# Smarttree_CMU_6.net
KiCad netlist of a schematic drawn in EAGLE
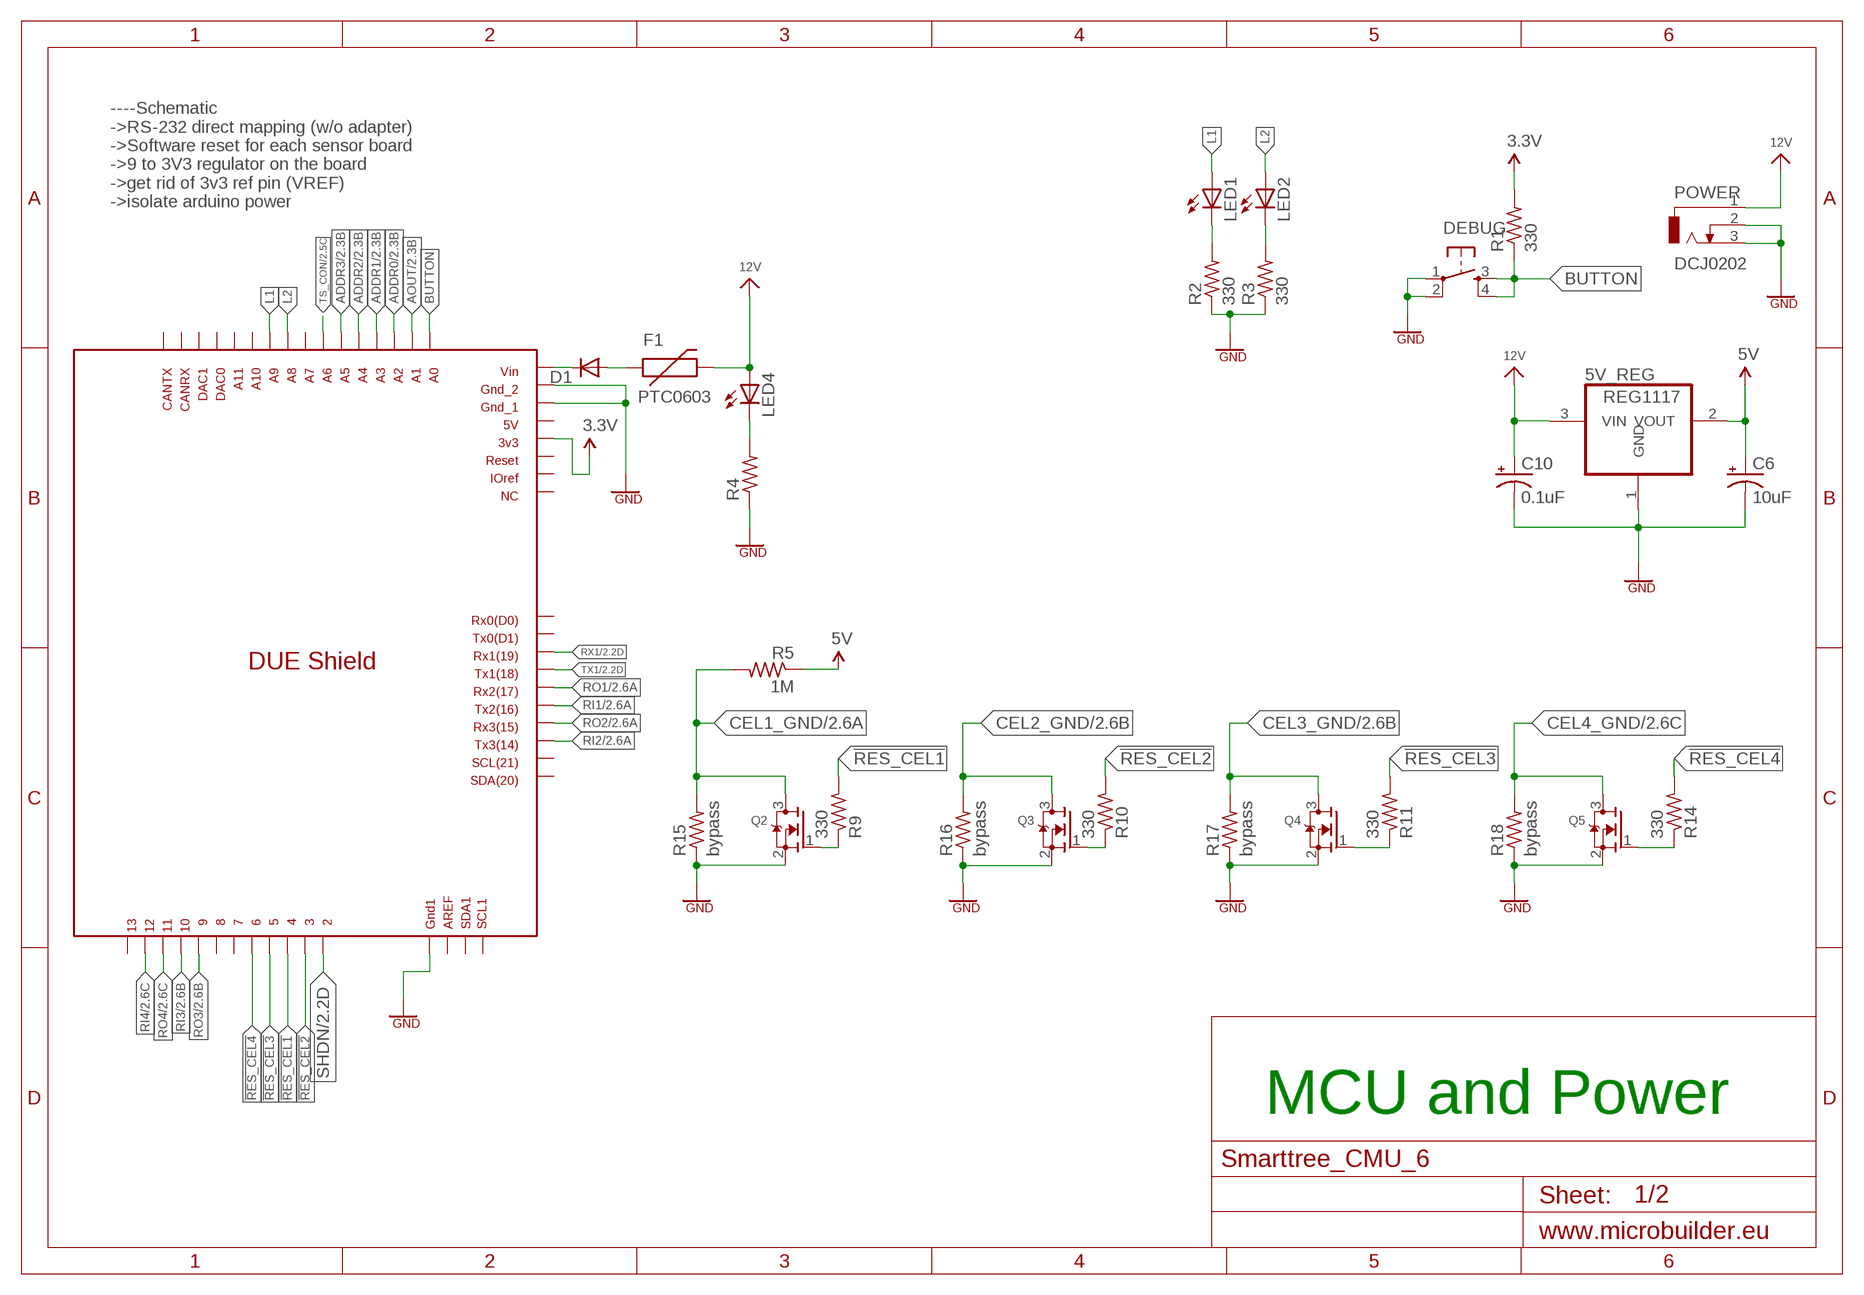
[diagram p0: schematic, sheet 1]
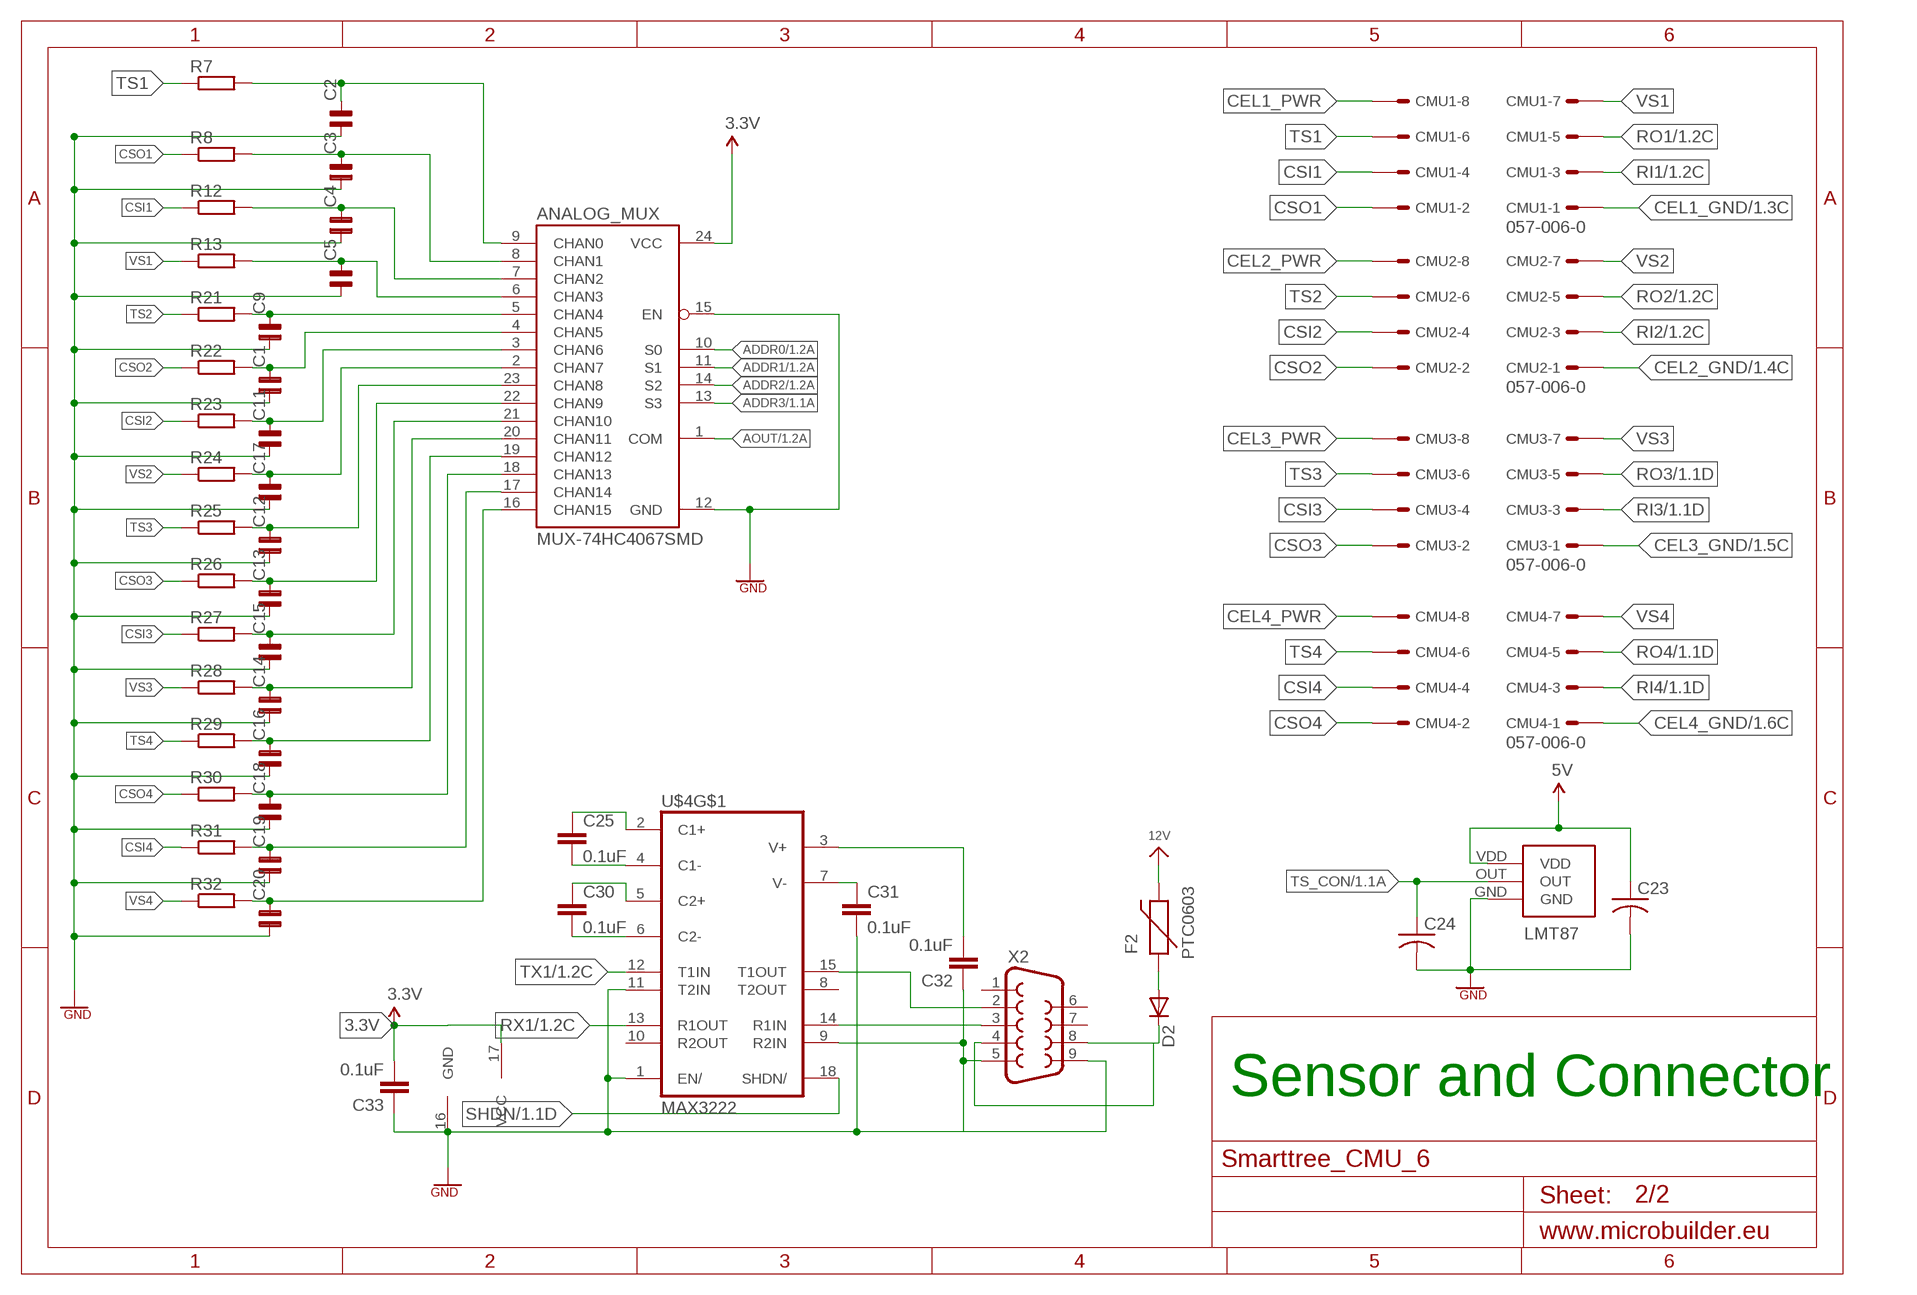
[diagram p1: schematic, sheet 2]

(export (version "E")
  (design (tool "Eeschema 10.0.6"))
  (components
    (comp (ref "5V_REG")
      (value "REG1117")
      (footprint "eagle-import:SOT223")
      (libsource (lib "eagle-import") (part "REG1117"))
    )
    (comp (ref "C6")
      (value "10uF")
      (footprint "eagle-import:EIA3216")
      (libsource (lib "eagle-import") (part "10UF-TANT"))
    )
    (comp (ref "C10")
      (value "0.1uF")
      (footprint "eagle-import:EIA3216")
      (libsource (lib "eagle-import") (part "10UF-TANT"))
    )
    (comp (ref "D1")
      (value "DIODE-SOD106-R")
      (footprint "eagle-import:SOD106-R")
      (libsource (lib "eagle-import") (part "DIODE-SOD106-R"))
    )
    (comp (ref "DEBUG")
      (value "TAC_SWITCHSMD")
      (footprint "eagle-import:TACTILE_SWITCH_SMD")
      (libsource (lib "eagle-import") (part "TAC_SWITCHSMD"))
    )
    (comp (ref "F1")
      (value "PTC0603")
      (footprint "eagle-import:0603")
      (libsource (lib "eagle-import") (part "PTC0603"))
    )
    (comp (ref "LED1")
      (value "LED-YELLOW0603")
      (footprint "eagle-import:LED-0603")
      (libsource (lib "eagle-import") (part "LED-YELLOW0603"))
    )
    (comp (ref "LED2")
      (value "LED-YELLOW0603")
      (footprint "eagle-import:LED-0603")
      (libsource (lib "eagle-import") (part "LED-YELLOW0603"))
    )
    (comp (ref "LED4")
      (value "LED-YELLOW0603")
      (footprint "eagle-import:LED-0603")
      (libsource (lib "eagle-import") (part "LED-YELLOW0603"))
    )
    (comp (ref "POWER")
      (value "DCJ0202")
      (footprint "eagle-import:DCJ0202")
      (libsource (lib "eagle-import") (part "DCJ0202"))
    )
    (comp (ref "Q2")
      (value "MOSFET-NREFLOW")
      (footprint "eagle-import:SOT23")
      (libsource (lib "eagle-import") (part "MOSFET-NREFLOW"))
    )
    (comp (ref "Q3")
      (value "MOSFET-NREFLOW")
      (footprint "eagle-import:SOT23")
      (libsource (lib "eagle-import") (part "MOSFET-NREFLOW"))
    )
    (comp (ref "Q4")
      (value "MOSFET-NREFLOW")
      (footprint "eagle-import:SOT23")
      (libsource (lib "eagle-import") (part "MOSFET-NREFLOW"))
    )
    (comp (ref "Q5")
      (value "MOSFET-NREFLOW")
      (footprint "eagle-import:SOT23")
      (libsource (lib "eagle-import") (part "MOSFET-NREFLOW"))
    )
    (comp (ref "R1")
      (value "330")
      (footprint "eagle-import:M0805")
      (libsource (lib "eagle-import") (part "R-US_M0805"))
    )
    (comp (ref "R2")
      (value "330")
      (footprint "eagle-import:M0805")
      (libsource (lib "eagle-import") (part "R-US_M0805"))
    )
    (comp (ref "R3")
      (value "330")
      (footprint "eagle-import:M0805")
      (libsource (lib "eagle-import") (part "R-US_M0805"))
    )
    (comp (ref "R4")
      (value "R-US_M0805")
      (footprint "eagle-import:M0805")
      (libsource (lib "eagle-import") (part "R-US_M0805"))
    )
    (comp (ref "R5")
      (value "1M")
      (footprint "eagle-import:R0805")
      (libsource (lib "eagle-import") (part "R-US_R0805"))
    )
    (comp (ref "R9")
      (value "330")
      (footprint "eagle-import:R0805")
      (libsource (lib "eagle-import") (part "R-US_R0805"))
    )
    (comp (ref "R10")
      (value "330")
      (footprint "eagle-import:R0805")
      (libsource (lib "eagle-import") (part "R-US_R0805"))
    )
    (comp (ref "R11")
      (value "330")
      (footprint "eagle-import:R0805")
      (libsource (lib "eagle-import") (part "R-US_R0805"))
    )
    (comp (ref "R14")
      (value "330")
      (footprint "eagle-import:R0805")
      (libsource (lib "eagle-import") (part "R-US_R0805"))
    )
    (comp (ref "R15")
      (value "bypass")
      (footprint "eagle-import:M0805")
      (libsource (lib "eagle-import") (part "R-US_M0805"))
    )
    (comp (ref "R16")
      (value "bypass")
      (footprint "eagle-import:M0805")
      (libsource (lib "eagle-import") (part "R-US_M0805"))
    )
    (comp (ref "R17")
      (value "bypass")
      (footprint "eagle-import:M0805")
      (libsource (lib "eagle-import") (part "R-US_M0805"))
    )
    (comp (ref "R18")
      (value "bypass")
      (footprint "eagle-import:M0805")
      (libsource (lib "eagle-import") (part "R-US_M0805"))
    )
    (comp (ref "U$1")
      (value "DUE(OUTLINE)")
      (footprint "eagle-import:DUE(NORMAL)")
      (libsource (lib "eagle-import") (part "DUE(OUTLINE)"))
    )
    (comp (ref "ANALOG_MUX")
      (value "MUX-74HC4067SMD")
      (footprint "eagle-import:SSOP24")
      (libsource (lib "eagle-import") (part "MUX-74HC4067SMD"))
    )
    (comp (ref "C1")
      (value "C-NP-SMD-0805")
      (footprint "eagle-import:C-0805")
      (libsource (lib "eagle-import") (part "C-NP-SMD-0805"))
    )
    (comp (ref "C2")
      (value "C-NP-SMD-0805")
      (footprint "eagle-import:C-0805")
      (libsource (lib "eagle-import") (part "C-NP-SMD-0805"))
    )
    (comp (ref "C3")
      (value "C-NP-SMD-0805")
      (footprint "eagle-import:C-0805")
      (libsource (lib "eagle-import") (part "C-NP-SMD-0805"))
    )
    (comp (ref "C4")
      (value "C-NP-SMD-0805")
      (footprint "eagle-import:C-0805")
      (libsource (lib "eagle-import") (part "C-NP-SMD-0805"))
    )
    (comp (ref "C5")
      (value "C-NP-SMD-0805")
      (footprint "eagle-import:C-0805")
      (libsource (lib "eagle-import") (part "C-NP-SMD-0805"))
    )
    (comp (ref "C9")
      (value "C-NP-SMD-0805")
      (footprint "eagle-import:C-0805")
      (libsource (lib "eagle-import") (part "C-NP-SMD-0805"))
    )
    (comp (ref "C11")
      (value "C-NP-SMD-0805")
      (footprint "eagle-import:C-0805")
      (libsource (lib "eagle-import") (part "C-NP-SMD-0805"))
    )
    (comp (ref "C12")
      (value "C-NP-SMD-0805")
      (footprint "eagle-import:C-0805")
      (libsource (lib "eagle-import") (part "C-NP-SMD-0805"))
    )
    (comp (ref "C13")
      (value "C-NP-SMD-0805")
      (footprint "eagle-import:C-0805")
      (libsource (lib "eagle-import") (part "C-NP-SMD-0805"))
    )
    (comp (ref "C14")
      (value "C-NP-SMD-0805")
      (footprint "eagle-import:C-0805")
      (libsource (lib "eagle-import") (part "C-NP-SMD-0805"))
    )
    (comp (ref "C15")
      (value "C-NP-SMD-0805")
      (footprint "eagle-import:C-0805")
      (libsource (lib "eagle-import") (part "C-NP-SMD-0805"))
    )
    (comp (ref "C16")
      (value "C-NP-SMD-0805")
      (footprint "eagle-import:C-0805")
      (libsource (lib "eagle-import") (part "C-NP-SMD-0805"))
    )
    (comp (ref "C17")
      (value "C-NP-SMD-0805")
      (footprint "eagle-import:C-0805")
      (libsource (lib "eagle-import") (part "C-NP-SMD-0805"))
    )
    (comp (ref "C18")
      (value "C-NP-SMD-0805")
      (footprint "eagle-import:C-0805")
      (libsource (lib "eagle-import") (part "C-NP-SMD-0805"))
    )
    (comp (ref "C19")
      (value "C-NP-SMD-0805")
      (footprint "eagle-import:C-0805")
      (libsource (lib "eagle-import") (part "C-NP-SMD-0805"))
    )
    (comp (ref "C20")
      (value "C-NP-SMD-0805")
      (footprint "eagle-import:C-0805")
      (libsource (lib "eagle-import") (part "C-NP-SMD-0805"))
    )
    (comp (ref "C23")
      (value "C-USC0805")
      (footprint "eagle-import:C0805")
      (libsource (lib "eagle-import") (part "C-USC0805"))
    )
    (comp (ref "C24")
      (value "C-USC0805")
      (footprint "eagle-import:C0805")
      (libsource (lib "eagle-import") (part "C-USC0805"))
    )
    (comp (ref "C25")
      (value "0.1uF")
      (footprint "eagle-import:0603-CAP")
      (libsource (lib "eagle-import") (part "CAP0603-CAP"))
    )
    (comp (ref "C30")
      (value "0.1uF")
      (footprint "eagle-import:0603-CAP")
      (libsource (lib "eagle-import") (part "CAP0603-CAP"))
    )
    (comp (ref "C31")
      (value "0.1uF")
      (footprint "eagle-import:0603-CAP")
      (libsource (lib "eagle-import") (part "CAP0603-CAP"))
    )
    (comp (ref "C32")
      (value "0.1uF")
      (footprint "eagle-import:0603-CAP")
      (libsource (lib "eagle-import") (part "CAP0603-CAP"))
    )
    (comp (ref "C33")
      (value "0.1uF")
      (footprint "eagle-import:0603-CAP")
      (libsource (lib "eagle-import") (part "CAP0603-CAP"))
    )
    (comp (ref "CMU1")
      (value "057-006-0")
      (footprint "eagle-import:057-006-0")
      (libsource (lib "eagle-import") (part "057-006-0"))
    )
    (comp (ref "CMU2")
      (value "057-006-0")
      (footprint "eagle-import:057-006-0")
      (libsource (lib "eagle-import") (part "057-006-0"))
    )
    (comp (ref "CMU3")
      (value "057-006-0")
      (footprint "eagle-import:057-006-0")
      (libsource (lib "eagle-import") (part "057-006-0"))
    )
    (comp (ref "CMU4")
      (value "057-006-0")
      (footprint "eagle-import:057-006-0")
      (libsource (lib "eagle-import") (part "057-006-0"))
    )
    (comp (ref "D2")
      (value "DIODE-SOD106-R")
      (footprint "eagle-import:SOD106-R")
      (libsource (lib "eagle-import") (part "DIODE-SOD106-R"))
    )
    (comp (ref "F2")
      (value "PTC0603")
      (footprint "eagle-import:0603")
      (libsource (lib "eagle-import") (part "PTC0603"))
    )
    (comp (ref "LMT87")
      (value "LMT87_PAC")
      (footprint "eagle-import:LMT87_TO")
      (libsource (lib "eagle-import") (part "LMT87_PAC"))
    )
    (comp (ref "R7")
      (value "R-EU_R0805W")
      (footprint "eagle-import:R0805W")
      (libsource (lib "eagle-import") (part "R-EU_R0805W"))
    )
    (comp (ref "R8")
      (value "R-EU_R0805W")
      (footprint "eagle-import:R0805W")
      (libsource (lib "eagle-import") (part "R-EU_R0805W"))
    )
    (comp (ref "R12")
      (value "R-EU_R0805W")
      (footprint "eagle-import:R0805W")
      (libsource (lib "eagle-import") (part "R-EU_R0805W"))
    )
    (comp (ref "R13")
      (value "R-EU_R0805W")
      (footprint "eagle-import:R0805W")
      (libsource (lib "eagle-import") (part "R-EU_R0805W"))
    )
    (comp (ref "R21")
      (value "R-EU_R0805W")
      (footprint "eagle-import:R0805W")
      (libsource (lib "eagle-import") (part "R-EU_R0805W"))
    )
    (comp (ref "R22")
      (value "R-EU_R0805W")
      (footprint "eagle-import:R0805W")
      (libsource (lib "eagle-import") (part "R-EU_R0805W"))
    )
    (comp (ref "R23")
      (value "R-EU_R0805W")
      (footprint "eagle-import:R0805W")
      (libsource (lib "eagle-import") (part "R-EU_R0805W"))
    )
    (comp (ref "R24")
      (value "R-EU_R0805W")
      (footprint "eagle-import:R0805W")
      (libsource (lib "eagle-import") (part "R-EU_R0805W"))
    )
    (comp (ref "R25")
      (value "R-EU_R0805W")
      (footprint "eagle-import:R0805W")
      (libsource (lib "eagle-import") (part "R-EU_R0805W"))
    )
    (comp (ref "R26")
      (value "R-EU_R0805W")
      (footprint "eagle-import:R0805W")
      (libsource (lib "eagle-import") (part "R-EU_R0805W"))
    )
    (comp (ref "R27")
      (value "R-EU_R0805W")
      (footprint "eagle-import:R0805W")
      (libsource (lib "eagle-import") (part "R-EU_R0805W"))
    )
    (comp (ref "R28")
      (value "R-EU_R0805W")
      (footprint "eagle-import:R0805W")
      (libsource (lib "eagle-import") (part "R-EU_R0805W"))
    )
    (comp (ref "R29")
      (value "R-EU_R0805W")
      (footprint "eagle-import:R0805W")
      (libsource (lib "eagle-import") (part "R-EU_R0805W"))
    )
    (comp (ref "R30")
      (value "R-EU_R0805W")
      (footprint "eagle-import:R0805W")
      (libsource (lib "eagle-import") (part "R-EU_R0805W"))
    )
    (comp (ref "R31")
      (value "R-EU_R0805W")
      (footprint "eagle-import:R0805W")
      (libsource (lib "eagle-import") (part "R-EU_R0805W"))
    )
    (comp (ref "R32")
      (value "R-EU_R0805W")
      (footprint "eagle-import:R0805W")
      (libsource (lib "eagle-import") (part "R-EU_R0805W"))
    )
    (comp (ref "U$4")
      (value "MAX3222")
      (footprint "eagle-import:SO18")
      (libsource (lib "eagle-import") (part "MAX3222"))
    )
    (comp (ref "X2")
      (value "DB9MALE")
      (footprint "eagle-import:DB9_MALE")
      (libsource (lib "eagle-import") (part "DB9MALE"))
    )
  )
  (nets
    (net (code "1") (name "3.3V") (class "Default")
      (node (ref "ANALOG_MUX") (pin "24") (pinfunction "VCC_24") (pintype "bidirectional"))
      (node (ref "C33") (pin "2") (pinfunction "2_2") (pintype "passive"))
      (node (ref "R1") (pin "2") (pinfunction "2_2") (pintype "passive"))
      (node (ref "U$1") (pin "3V3") (pinfunction "3V3_3V3") (pintype "bidirectional"))
      (node (ref "U$4") (pin "17") (pinfunction "VCC_17") (pintype "bidirectional"))
    )
    (net (code "2") (name "5V") (class "Default")
      (node (ref "5V_REG") (pin "2") (pinfunction "VOUT_2") (pintype "output"))
      (node (ref "C23") (pin "1") (pinfunction "1_1") (pintype "passive"))
      (node (ref "C6") (pin "A") (pinfunction "+_A") (pintype "passive"))
      (node (ref "LMT87") (pin "VDD") (pinfunction "VDD_VDD") (pintype "bidirectional"))
      (node (ref "R5") (pin "1") (pinfunction "1_1") (pintype "passive"))
    )
    (net (code "3") (name "12V") (class "Default")
      (node (ref "5V_REG") (pin "3") (pinfunction "VIN_3") (pintype "input"))
      (node (ref "C10") (pin "A") (pinfunction "+_A") (pintype "passive"))
      (node (ref "F1") (pin "2") (pinfunction "2_2") (pintype "bidirectional"))
      (node (ref "F2") (pin "2") (pinfunction "2_2") (pintype "bidirectional"))
      (node (ref "LED4") (pin "A") (pinfunction "A_A") (pintype "passive"))
      (node (ref "POWER") (pin "1") (pinfunction "1_1") (pintype "passive"))
    )
    (net (code "4") (name "ADDR0") (class "Default")
      (node (ref "ANALOG_MUX") (pin "10") (pinfunction "S0_10") (pintype "input"))
      (node (ref "U$1") (pin "A2") (pinfunction "A2_A2") (pintype "bidirectional"))
    )
    (net (code "5") (name "ADDR1") (class "Default")
      (node (ref "ANALOG_MUX") (pin "11") (pinfunction "S1_11") (pintype "input"))
      (node (ref "U$1") (pin "A3") (pinfunction "A3_A3") (pintype "bidirectional"))
    )
    (net (code "6") (name "ADDR2") (class "Default")
      (node (ref "ANALOG_MUX") (pin "14") (pinfunction "S2_14") (pintype "input"))
      (node (ref "U$1") (pin "A4") (pinfunction "A4_A4") (pintype "bidirectional"))
    )
    (net (code "7") (name "ADDR3") (class "Default")
      (node (ref "ANALOG_MUX") (pin "13") (pinfunction "S3_13") (pintype "input"))
      (node (ref "U$1") (pin "A5") (pinfunction "A5_A5") (pintype "bidirectional"))
    )
    (net (code "8") (name "AOUT") (class "Default")
      (node (ref "ANALOG_MUX") (pin "1") (pinfunction "COM_1") (pintype "bidirectional"))
      (node (ref "U$1") (pin "A1") (pinfunction "A1_A1") (pintype "bidirectional"))
    )
    (net (code "9") (name "BUTTON") (class "Default")
      (node (ref "DEBUG") (pin "3") (pinfunction "3_3") (pintype "passive"))
      (node (ref "DEBUG") (pin "4") (pinfunction "4_4") (pintype "passive"))
      (node (ref "R1") (pin "1") (pinfunction "1_1") (pintype "passive"))
      (node (ref "U$1") (pin "A0") (pinfunction "A0_A0") (pintype "bidirectional"))
    )
    (net (code "10") (name "CEL1_GND") (class "Default")
      (node (ref "CMU1") (pin "1") (pinfunction "S_1") (pintype "passive"))
      (node (ref "Q2") (pin "3") (pinfunction "D_3") (pintype "bidirectional"))
      (node (ref "R15") (pin "2") (pinfunction "2_2") (pintype "passive"))
      (node (ref "R5") (pin "2") (pinfunction "2_2") (pintype "passive"))
    )
    (net (code "11") (name "CEL1_PWR") (class "Default")
      (node (ref "CMU1") (pin "7") (pinfunction "S_7") (pintype "passive"))
    )
    (net (code "12") (name "CEL2_GND") (class "Default")
      (node (ref "CMU2") (pin "1") (pinfunction "S_1") (pintype "passive"))
      (node (ref "Q3") (pin "3") (pinfunction "D_3") (pintype "bidirectional"))
      (node (ref "R16") (pin "2") (pinfunction "2_2") (pintype "passive"))
    )
    (net (code "13") (name "CEL2_PWR") (class "Default")
      (node (ref "CMU2") (pin "7") (pinfunction "S_7") (pintype "passive"))
    )
    (net (code "14") (name "CEL3_GND") (class "Default")
      (node (ref "CMU3") (pin "1") (pinfunction "S_1") (pintype "passive"))
      (node (ref "Q4") (pin "3") (pinfunction "D_3") (pintype "bidirectional"))
      (node (ref "R17") (pin "2") (pinfunction "2_2") (pintype "passive"))
    )
    (net (code "15") (name "CEL3_PWR") (class "Default")
      (node (ref "CMU3") (pin "7") (pinfunction "S_7") (pintype "passive"))
    )
    (net (code "16") (name "CEL4_GND") (class "Default")
      (node (ref "CMU4") (pin "1") (pinfunction "S_1") (pintype "passive"))
      (node (ref "Q5") (pin "3") (pinfunction "D_3") (pintype "bidirectional"))
      (node (ref "R18") (pin "2") (pinfunction "2_2") (pintype "passive"))
    )
    (net (code "17") (name "CEL4_PWR") (class "Default")
      (node (ref "CMU4") (pin "7") (pinfunction "S_7") (pintype "passive"))
    )
    (net (code "18") (name "CSI1") (class "Default")
      (node (ref "CMU1") (pin "4") (pinfunction "S_4") (pintype "passive"))
      (node (ref "R12") (pin "1") (pinfunction "1_1") (pintype "passive"))
    )
    (net (code "19") (name "CSI2") (class "Default")
      (node (ref "CMU2") (pin "4") (pinfunction "S_4") (pintype "passive"))
      (node (ref "R23") (pin "1") (pinfunction "1_1") (pintype "passive"))
    )
    (net (code "20") (name "CSI3") (class "Default")
      (node (ref "CMU3") (pin "4") (pinfunction "S_4") (pintype "passive"))
      (node (ref "R27") (pin "1") (pinfunction "1_1") (pintype "passive"))
    )
    (net (code "21") (name "CSI4") (class "Default")
      (node (ref "CMU4") (pin "4") (pinfunction "S_4") (pintype "passive"))
      (node (ref "R31") (pin "1") (pinfunction "1_1") (pintype "passive"))
    )
    (net (code "22") (name "CSO1") (class "Default")
      (node (ref "CMU1") (pin "2") (pinfunction "S_2") (pintype "passive"))
      (node (ref "R8") (pin "1") (pinfunction "1_1") (pintype "passive"))
    )
    (net (code "23") (name "CSO2") (class "Default")
      (node (ref "CMU2") (pin "2") (pinfunction "S_2") (pintype "passive"))
      (node (ref "R22") (pin "1") (pinfunction "1_1") (pintype "passive"))
    )
    (net (code "24") (name "CSO3") (class "Default")
      (node (ref "CMU3") (pin "2") (pinfunction "S_2") (pintype "passive"))
      (node (ref "R26") (pin "1") (pinfunction "1_1") (pintype "passive"))
    )
    (net (code "25") (name "CSO4") (class "Default")
      (node (ref "CMU4") (pin "2") (pinfunction "S_2") (pintype "passive"))
      (node (ref "R30") (pin "1") (pinfunction "1_1") (pintype "passive"))
    )
    (net (code "26") (name "GND") (class "Default")
      (node (ref "5V_REG") (pin "1") (pinfunction "GND_1") (pintype "power_in"))
      (node (ref "ANALOG_MUX") (pin "12") (pinfunction "GND_12") (pintype "bidirectional"))
      (node (ref "ANALOG_MUX") (pin "15") (pinfunction "EN_15") (pintype "input"))
      (node (ref "C1") (pin "1") (pinfunction "1_1") (pintype "passive"))
      (node (ref "C10") (pin "C") (pinfunction "-_C") (pintype "passive"))
      (node (ref "C11") (pin "1") (pinfunction "1_1") (pintype "passive"))
      (node (ref "C12") (pin "1") (pinfunction "1_1") (pintype "passive"))
      (node (ref "C13") (pin "1") (pinfunction "1_1") (pintype "passive"))
      (node (ref "C14") (pin "1") (pinfunction "1_1") (pintype "passive"))
      (node (ref "C15") (pin "1") (pinfunction "1_1") (pintype "passive"))
      (node (ref "C16") (pin "1") (pinfunction "1_1") (pintype "passive"))
      (node (ref "C17") (pin "1") (pinfunction "1_1") (pintype "passive"))
      (node (ref "C18") (pin "1") (pinfunction "1_1") (pintype "passive"))
      (node (ref "C19") (pin "1") (pinfunction "1_1") (pintype "passive"))
      (node (ref "C2") (pin "1") (pinfunction "1_1") (pintype "passive"))
      (node (ref "C20") (pin "1") (pinfunction "1_1") (pintype "passive"))
      (node (ref "C23") (pin "2") (pinfunction "2_2") (pintype "passive"))
      (node (ref "C24") (pin "2") (pinfunction "2_2") (pintype "passive"))
      (node (ref "C3") (pin "1") (pinfunction "1_1") (pintype "passive"))
      (node (ref "C31") (pin "2") (pinfunction "2_2") (pintype "passive"))
      (node (ref "C32") (pin "1") (pinfunction "1_1") (pintype "passive"))
      (node (ref "C33") (pin "1") (pinfunction "1_1") (pintype "passive"))
      (node (ref "C4") (pin "1") (pinfunction "1_1") (pintype "passive"))
      (node (ref "C5") (pin "1") (pinfunction "1_1") (pintype "passive"))
      (node (ref "C6") (pin "C") (pinfunction "-_C") (pintype "passive"))
      (node (ref "C9") (pin "1") (pinfunction "1_1") (pintype "passive"))
      (node (ref "DEBUG") (pin "1") (pinfunction "1_1") (pintype "passive"))
      (node (ref "DEBUG") (pin "2") (pinfunction "2_2") (pintype "passive"))
      (node (ref "LMT87") (pin "GND") (pinfunction "GND_GND") (pintype "bidirectional"))
      (node (ref "POWER") (pin "2") (pinfunction "2_2") (pintype "passive"))
      (node (ref "POWER") (pin "3") (pinfunction "3_3") (pintype "passive"))
      (node (ref "Q2") (pin "2") (pinfunction "S_2") (pintype "bidirectional"))
      (node (ref "Q3") (pin "2") (pinfunction "S_2") (pintype "bidirectional"))
      (node (ref "Q4") (pin "2") (pinfunction "S_2") (pintype "bidirectional"))
      (node (ref "Q5") (pin "2") (pinfunction "S_2") (pintype "bidirectional"))
      (node (ref "R15") (pin "1") (pinfunction "1_1") (pintype "passive"))
      (node (ref "R16") (pin "1") (pinfunction "1_1") (pintype "passive"))
      (node (ref "R17") (pin "1") (pinfunction "1_1") (pintype "passive"))
      (node (ref "R18") (pin "1") (pinfunction "1_1") (pintype "passive"))
      (node (ref "R2") (pin "1") (pinfunction "1_1") (pintype "passive"))
      (node (ref "R3") (pin "1") (pinfunction "1_1") (pintype "passive"))
      (node (ref "R4") (pin "1") (pinfunction "1_1") (pintype "passive"))
      (node (ref "U$1") (pin "GND1") (pinfunction "GND1_GND1") (pintype "bidirectional"))
      (node (ref "U$1") (pin "GND_1") (pinfunction "GND_1_GND_1") (pintype "bidirectional"))
      (node (ref "U$1") (pin "GND_2") (pinfunction "GND_2_GND_2") (pintype "bidirectional"))
      (node (ref "U$4") (pin "1") (pinfunction "EN/_1") (pintype "input"))
      (node (ref "U$4") (pin "11") (pinfunction "T2IN_11") (pintype "input"))
      (node (ref "U$4") (pin "16") (pinfunction "GND_16") (pintype "bidirectional"))
      (node (ref "U$4") (pin "9") (pinfunction "R2IN_9") (pintype "input"))
      (node (ref "X2") (pin "5") (pinfunction "5_5") (pintype "passive"))
      (node (ref "X2") (pin "9") (pinfunction "9_9") (pintype "passive"))
    )
    (net (code "27") (name "L1") (class "Default")
      (node (ref "LED1") (pin "A") (pinfunction "A_A") (pintype "passive"))
      (node (ref "U$1") (pin "A9") (pinfunction "A9_A9") (pintype "bidirectional"))
    )
    (net (code "28") (name "L2") (class "Default")
      (node (ref "LED2") (pin "A") (pinfunction "A_A") (pintype "passive"))
      (node (ref "U$1") (pin "A8") (pinfunction "A8_A8") (pintype "bidirectional"))
    )
    (net (code "29") (name "Net-(ANALOG_MUX-CHAN0)") (class "Default")
      (node (ref "ANALOG_MUX") (pin "9") (pinfunction "CHAN0_9") (pintype "bidirectional"))
      (node (ref "C2") (pin "2") (pinfunction "2_2") (pintype "passive"))
      (node (ref "R7") (pin "2") (pinfunction "2_2") (pintype "passive"))
    )
    (net (code "30") (name "Net-(ANALOG_MUX-CHAN1)") (class "Default")
      (node (ref "ANALOG_MUX") (pin "8") (pinfunction "CHAN1_8") (pintype "bidirectional"))
      (node (ref "C3") (pin "2") (pinfunction "2_2") (pintype "passive"))
      (node (ref "R8") (pin "2") (pinfunction "2_2") (pintype "passive"))
    )
    (net (code "31") (name "Net-(ANALOG_MUX-CHAN2)") (class "Default")
      (node (ref "ANALOG_MUX") (pin "7") (pinfunction "CHAN2_7") (pintype "bidirectional"))
      (node (ref "C4") (pin "2") (pinfunction "2_2") (pintype "passive"))
      (node (ref "R12") (pin "2") (pinfunction "2_2") (pintype "passive"))
    )
    (net (code "32") (name "Net-(ANALOG_MUX-CHAN3)") (class "Default")
      (node (ref "ANALOG_MUX") (pin "6") (pinfunction "CHAN3_6") (pintype "bidirectional"))
      (node (ref "C5") (pin "2") (pinfunction "2_2") (pintype "passive"))
      (node (ref "R13") (pin "2") (pinfunction "2_2") (pintype "passive"))
    )
    (net (code "33") (name "Net-(ANALOG_MUX-CHAN4)") (class "Default")
      (node (ref "ANALOG_MUX") (pin "5") (pinfunction "CHAN4_5") (pintype "bidirectional"))
      (node (ref "C9") (pin "2") (pinfunction "2_2") (pintype "passive"))
      (node (ref "R21") (pin "2") (pinfunction "2_2") (pintype "passive"))
    )
    (net (code "34") (name "Net-(ANALOG_MUX-CHAN5)") (class "Default")
      (node (ref "ANALOG_MUX") (pin "4") (pinfunction "CHAN5_4") (pintype "bidirectional"))
      (node (ref "C1") (pin "2") (pinfunction "2_2") (pintype "passive"))
      (node (ref "R22") (pin "2") (pinfunction "2_2") (pintype "passive"))
    )
    (net (code "35") (name "Net-(ANALOG_MUX-CHAN6)") (class "Default")
      (node (ref "ANALOG_MUX") (pin "3") (pinfunction "CHAN6_3") (pintype "bidirectional"))
      (node (ref "C11") (pin "2") (pinfunction "2_2") (pintype "passive"))
      (node (ref "R23") (pin "2") (pinfunction "2_2") (pintype "passive"))
    )
    (net (code "36") (name "Net-(ANALOG_MUX-CHAN7)") (class "Default")
      (node (ref "ANALOG_MUX") (pin "2") (pinfunction "CHAN7_2") (pintype "bidirectional"))
      (node (ref "C17") (pin "2") (pinfunction "2_2") (pintype "passive"))
      (node (ref "R24") (pin "2") (pinfunction "2_2") (pintype "passive"))
    )
    (net (code "37") (name "Net-(ANALOG_MUX-CHAN8)") (class "Default")
      (node (ref "ANALOG_MUX") (pin "23") (pinfunction "CHAN8_23") (pintype "bidirectional"))
      (node (ref "C12") (pin "2") (pinfunction "2_2") (pintype "passive"))
      (node (ref "R25") (pin "2") (pinfunction "2_2") (pintype "passive"))
    )
    (net (code "38") (name "Net-(ANALOG_MUX-CHAN9)") (class "Default")
      (node (ref "ANALOG_MUX") (pin "22") (pinfunction "CHAN9_22") (pintype "bidirectional"))
      (node (ref "C13") (pin "2") (pinfunction "2_2") (pintype "passive"))
      (node (ref "R26") (pin "2") (pinfunction "2_2") (pintype "passive"))
    )
    (net (code "39") (name "Net-(ANALOG_MUX-CHAN10)") (class "Default")
      (node (ref "ANALOG_MUX") (pin "21") (pinfunction "CHAN10_21") (pintype "bidirectional"))
      (node (ref "C15") (pin "2") (pinfunction "2_2") (pintype "passive"))
      (node (ref "R27") (pin "2") (pinfunction "2_2") (pintype "passive"))
    )
    (net (code "40") (name "Net-(ANALOG_MUX-CHAN11)") (class "Default")
      (node (ref "ANALOG_MUX") (pin "20") (pinfunction "CHAN11_20") (pintype "bidirectional"))
      (node (ref "C14") (pin "2") (pinfunction "2_2") (pintype "passive"))
      (node (ref "R28") (pin "2") (pinfunction "2_2") (pintype "passive"))
    )
    (net (code "41") (name "Net-(ANALOG_MUX-CHAN12)") (class "Default")
      (node (ref "ANALOG_MUX") (pin "19") (pinfunction "CHAN12_19") (pintype "bidirectional"))
      (node (ref "C16") (pin "2") (pinfunction "2_2") (pintype "passive"))
      (node (ref "R29") (pin "2") (pinfunction "2_2") (pintype "passive"))
    )
    (net (code "42") (name "Net-(ANALOG_MUX-CHAN13)") (class "Default")
      (node (ref "ANALOG_MUX") (pin "18") (pinfunction "CHAN13_18") (pintype "bidirectional"))
      (node (ref "C18") (pin "2") (pinfunction "2_2") (pintype "passive"))
      (node (ref "R30") (pin "2") (pinfunction "2_2") (pintype "passive"))
    )
    (net (code "43") (name "Net-(ANALOG_MUX-CHAN14)") (class "Default")
      (node (ref "ANALOG_MUX") (pin "17") (pinfunction "CHAN14_17") (pintype "bidirectional"))
      (node (ref "C19") (pin "2") (pinfunction "2_2") (pintype "passive"))
      (node (ref "R31") (pin "2") (pinfunction "2_2") (pintype "passive"))
    )
    (net (code "44") (name "Net-(ANALOG_MUX-CHAN15)") (class "Default")
      (node (ref "ANALOG_MUX") (pin "16") (pinfunction "CHAN15_16") (pintype "bidirectional"))
      (node (ref "C20") (pin "2") (pinfunction "2_2") (pintype "passive"))
      (node (ref "R32") (pin "2") (pinfunction "2_2") (pintype "passive"))
    )
    (net (code "45") (name "Net-(D1-PadA)") (class "Default")
      (node (ref "D1") (pin "A") (pinfunction "A_A") (pintype "passive"))
      (node (ref "F1") (pin "1") (pinfunction "1_1") (pintype "bidirectional"))
    )
    (net (code "46") (name "Net-(D1-PadC)") (class "Default")
      (node (ref "D1") (pin "C") (pinfunction "C_C") (pintype "passive"))
      (node (ref "U$1") (pin "VIN") (pinfunction "VIN_VIN") (pintype "bidirectional"))
    )
    (net (code "47") (name "Net-(D2-PadA)") (class "Default")
      (node (ref "D2") (pin "A") (pinfunction "A_A") (pintype "passive"))
      (node (ref "F2") (pin "1") (pinfunction "1_1") (pintype "bidirectional"))
    )
    (net (code "48") (name "Net-(D2-PadC)") (class "Default")
      (node (ref "D2") (pin "C") (pinfunction "C_C") (pintype "passive"))
      (node (ref "X2") (pin "4") (pinfunction "4_4") (pintype "passive"))
      (node (ref "X2") (pin "8") (pinfunction "8_8") (pintype "passive"))
    )
    (net (code "49") (name "Net-(LED1-PadC)") (class "Default")
      (node (ref "LED1") (pin "C") (pinfunction "C_C") (pintype "passive"))
      (node (ref "R2") (pin "2") (pinfunction "2_2") (pintype "passive"))
    )
    (net (code "50") (name "Net-(LED2-PadC)") (class "Default")
      (node (ref "LED2") (pin "C") (pinfunction "C_C") (pintype "passive"))
      (node (ref "R3") (pin "2") (pinfunction "2_2") (pintype "passive"))
    )
    (net (code "51") (name "Net-(LED4-PadC)") (class "Default")
      (node (ref "LED4") (pin "C") (pinfunction "C_C") (pintype "passive"))
      (node (ref "R4") (pin "2") (pinfunction "2_2") (pintype "passive"))
    )
    (net (code "52") (name "Net-(Q2-G)") (class "Default")
      (node (ref "Q2") (pin "1") (pinfunction "G_1") (pintype "bidirectional"))
      (node (ref "R9") (pin "1") (pinfunction "1_1") (pintype "passive"))
    )
    (net (code "53") (name "Net-(Q3-G)") (class "Default")
      (node (ref "Q3") (pin "1") (pinfunction "G_1") (pintype "bidirectional"))
      (node (ref "R10") (pin "1") (pinfunction "1_1") (pintype "passive"))
    )
    (net (code "54") (name "Net-(Q4-G)") (class "Default")
      (node (ref "Q4") (pin "1") (pinfunction "G_1") (pintype "bidirectional"))
      (node (ref "R11") (pin "1") (pinfunction "1_1") (pintype "passive"))
    )
    (net (code "55") (name "Net-(Q5-G)") (class "Default")
      (node (ref "Q5") (pin "1") (pinfunction "G_1") (pintype "bidirectional"))
      (node (ref "R14") (pin "1") (pinfunction "1_1") (pintype "passive"))
    )
    (net (code "56") (name "Net-(U$4A-C1+)") (class "Default")
      (node (ref "C25") (pin "1") (pinfunction "1_1") (pintype "passive"))
      (node (ref "U$4") (pin "2") (pinfunction "C1+_2") (pintype "passive"))
    )
    (net (code "57") (name "Net-(U$4A-C1-)") (class "Default")
      (node (ref "C25") (pin "2") (pinfunction "2_2") (pintype "passive"))
      (node (ref "U$4") (pin "4") (pinfunction "C1-_4") (pintype "passive"))
    )
    (net (code "58") (name "Net-(U$4A-C2+)") (class "Default")
      (node (ref "C30") (pin "1") (pinfunction "1_1") (pintype "passive"))
      (node (ref "U$4") (pin "5") (pinfunction "C2+_5") (pintype "passive"))
    )
    (net (code "59") (name "Net-(U$4A-C2-)") (class "Default")
      (node (ref "C30") (pin "2") (pinfunction "2_2") (pintype "passive"))
      (node (ref "U$4") (pin "6") (pinfunction "C2-_6") (pintype "passive"))
    )
    (net (code "60") (name "Net-(U$4A-R1IN)") (class "Default")
      (node (ref "U$4") (pin "14") (pinfunction "R1IN_14") (pintype "input"))
      (node (ref "X2") (pin "3") (pinfunction "3_3") (pintype "passive"))
    )
    (net (code "61") (name "Net-(U$4A-T1OUT)") (class "Default")
      (node (ref "U$4") (pin "15") (pinfunction "T1OUT_15") (pintype "output"))
      (node (ref "X2") (pin "2") (pinfunction "2_2") (pintype "passive"))
    )
    (net (code "62") (name "Net-(U$4A-V+)") (class "Default")
      (node (ref "C32") (pin "2") (pinfunction "2_2") (pintype "passive"))
      (node (ref "U$4") (pin "3") (pinfunction "V+_3") (pintype "passive"))
    )
    (net (code "63") (name "Net-(U$4A-V-)") (class "Default")
      (node (ref "C31") (pin "1") (pinfunction "1_1") (pintype "passive"))
      (node (ref "U$4") (pin "7") (pinfunction "V-_7") (pintype "passive"))
    )
    (net (code "64") (name "RI1") (class "Default")
      (node (ref "CMU1") (pin "3") (pinfunction "S_3") (pintype "passive"))
      (node (ref "U$1") (pin "TX2") (pinfunction "TX2_TX2") (pintype "bidirectional"))
    )
    (net (code "65") (name "RI2") (class "Default")
      (node (ref "CMU2") (pin "3") (pinfunction "S_3") (pintype "passive"))
      (node (ref "U$1") (pin "TX3") (pinfunction "TX3_TX3") (pintype "bidirectional"))
    )
    (net (code "66") (name "RI3") (class "Default")
      (node (ref "CMU3") (pin "3") (pinfunction "S_3") (pintype "passive"))
      (node (ref "U$1") (pin "10") (pinfunction "10_10") (pintype "bidirectional"))
    )
    (net (code "67") (name "RI4") (class "Default")
      (node (ref "CMU4") (pin "3") (pinfunction "S_3") (pintype "passive"))
      (node (ref "U$1") (pin "12") (pinfunction "12_12") (pintype "bidirectional"))
    )
    (net (code "68") (name "RO1") (class "Default")
      (node (ref "CMU1") (pin "5") (pinfunction "S_5") (pintype "passive"))
      (node (ref "U$1") (pin "RX2") (pinfunction "RX2_RX2") (pintype "bidirectional"))
    )
    (net (code "69") (name "RO2") (class "Default")
      (node (ref "CMU2") (pin "5") (pinfunction "S_5") (pintype "passive"))
      (node (ref "U$1") (pin "RX3") (pinfunction "RX3_RX3") (pintype "bidirectional"))
    )
    (net (code "70") (name "RO3") (class "Default")
      (node (ref "CMU3") (pin "5") (pinfunction "S_5") (pintype "passive"))
      (node (ref "U$1") (pin "9") (pinfunction "9_9") (pintype "bidirectional"))
    )
    (net (code "71") (name "RO4") (class "Default")
      (node (ref "CMU4") (pin "5") (pinfunction "S_5") (pintype "passive"))
      (node (ref "U$1") (pin "11") (pinfunction "11_11") (pintype "bidirectional"))
    )
    (net (code "72") (name "RX1") (class "Default")
      (node (ref "U$1") (pin "RX1") (pinfunction "RX1_RX1") (pintype "bidirectional"))
      (node (ref "U$4") (pin "13") (pinfunction "R1OUT_13") (pintype "output"))
    )
    (net (code "73") (name "SHDN") (class "Default")
      (node (ref "U$1") (pin "2") (pinfunction "2_2") (pintype "bidirectional"))
      (node (ref "U$4") (pin "18") (pinfunction "SHDN/_18") (pintype "input"))
    )
    (net (code "74") (name "TS1") (class "Default")
      (node (ref "CMU1") (pin "6") (pinfunction "S_6") (pintype "passive"))
      (node (ref "R7") (pin "1") (pinfunction "1_1") (pintype "passive"))
    )
    (net (code "75") (name "TS2") (class "Default")
      (node (ref "CMU2") (pin "6") (pinfunction "S_6") (pintype "passive"))
      (node (ref "R21") (pin "1") (pinfunction "1_1") (pintype "passive"))
    )
    (net (code "76") (name "TS3") (class "Default")
      (node (ref "CMU3") (pin "6") (pinfunction "S_6") (pintype "passive"))
      (node (ref "R25") (pin "1") (pinfunction "1_1") (pintype "passive"))
    )
    (net (code "77") (name "TS4") (class "Default")
      (node (ref "CMU4") (pin "6") (pinfunction "S_6") (pintype "passive"))
      (node (ref "R29") (pin "1") (pinfunction "1_1") (pintype "passive"))
    )
    (net (code "78") (name "TS_CON") (class "Default")
      (node (ref "C24") (pin "1") (pinfunction "1_1") (pintype "passive"))
      (node (ref "LMT87") (pin "OUT") (pinfunction "OUT_OUT") (pintype "bidirectional"))
      (node (ref "U$1") (pin "A6") (pinfunction "A6_A6") (pintype "bidirectional"))
    )
    (net (code "79") (name "TX1") (class "Default")
      (node (ref "U$1") (pin "TX1") (pinfunction "TX1_TX1") (pintype "bidirectional"))
      (node (ref "U$4") (pin "12") (pinfunction "T1IN_12") (pintype "input"))
    )
    (net (code "80") (name "VS1") (class "Default")
      (node (ref "CMU1") (pin "8") (pinfunction "S_8") (pintype "passive"))
      (node (ref "R13") (pin "1") (pinfunction "1_1") (pintype "passive"))
    )
    (net (code "81") (name "VS2") (class "Default")
      (node (ref "CMU2") (pin "8") (pinfunction "S_8") (pintype "passive"))
      (node (ref "R24") (pin "1") (pinfunction "1_1") (pintype "passive"))
    )
    (net (code "82") (name "VS3") (class "Default")
      (node (ref "CMU3") (pin "8") (pinfunction "S_8") (pintype "passive"))
      (node (ref "R28") (pin "1") (pinfunction "1_1") (pintype "passive"))
    )
    (net (code "83") (name "VS4") (class "Default")
      (node (ref "CMU4") (pin "8") (pinfunction "S_8") (pintype "passive"))
      (node (ref "R32") (pin "1") (pinfunction "1_1") (pintype "passive"))
    )
    (net (code "84") (name "unconnected-(U$1-Pad5V)") (class "Default")
      (node (ref "U$1") (pin "5V") (pinfunction "5V_5V") (pintype "bidirectional"))
    )
    (net (code "85") (name "unconnected-(U$1-Pad7)") (class "Default")
      (node (ref "U$1") (pin "7") (pinfunction "7_7") (pintype "bidirectional"))
    )
    (net (code "86") (name "unconnected-(U$1-Pad8)") (class "Default")
      (node (ref "U$1") (pin "8") (pinfunction "8_8") (pintype "bidirectional"))
    )
    (net (code "87") (name "unconnected-(U$1-Pad13)") (class "Default")
      (node (ref "U$1") (pin "13") (pinfunction "13_13") (pintype "bidirectional"))
    )
    (net (code "88") (name "unconnected-(U$1-PadA7)") (class "Default")
      (node (ref "U$1") (pin "A7") (pinfunction "A7_A7") (pintype "bidirectional"))
    )
    (net (code "89") (name "unconnected-(U$1-PadA10)") (class "Default")
      (node (ref "U$1") (pin "A10") (pinfunction "A10_A10") (pintype "bidirectional"))
    )
    (net (code "90") (name "unconnected-(U$1-PadA11)") (class "Default")
      (node (ref "U$1") (pin "A11") (pinfunction "A11_A11") (pintype "bidirectional"))
    )
    (net (code "91") (name "unconnected-(U$1-PadAREF)") (class "Default")
      (node (ref "U$1") (pin "AREF") (pinfunction "AREF_AREF") (pintype "bidirectional"))
    )
    (net (code "92") (name "unconnected-(U$1-PadCANRX)") (class "Default")
      (node (ref "U$1") (pin "CANRX") (pinfunction "CANRX_CANRX") (pintype "bidirectional"))
    )
    (net (code "93") (name "unconnected-(U$1-PadCANTX)") (class "Default")
      (node (ref "U$1") (pin "CANTX") (pinfunction "CANTX_CANTX") (pintype "bidirectional"))
    )
    (net (code "94") (name "unconnected-(U$1-PadDAC0)") (class "Default")
      (node (ref "U$1") (pin "DAC0") (pinfunction "DAC0_DAC0") (pintype "bidirectional"))
    )
    (net (code "95") (name "unconnected-(U$1-PadDAC1)") (class "Default")
      (node (ref "U$1") (pin "DAC1") (pinfunction "DAC1_DAC1") (pintype "bidirectional"))
    )
    (net (code "96") (name "unconnected-(U$1-PadIOREF)") (class "Default")
      (node (ref "U$1") (pin "IOREF") (pinfunction "IOREF_IOREF") (pintype "bidirectional"))
    )
    (net (code "97") (name "unconnected-(U$1-PadNC)") (class "Default")
      (node (ref "U$1") (pin "NC") (pinfunction "NC_NC") (pintype "bidirectional"))
    )
    (net (code "98") (name "unconnected-(U$1-PadRESET)") (class "Default")
      (node (ref "U$1") (pin "RESET") (pinfunction "RESET_RESET") (pintype "bidirectional"))
    )
    (net (code "99") (name "unconnected-(U$1-PadRX0)") (class "Default")
      (node (ref "U$1") (pin "RX0") (pinfunction "RX0_RX0") (pintype "bidirectional"))
    )
    (net (code "100") (name "unconnected-(U$1-PadSCL)") (class "Default")
      (node (ref "U$1") (pin "SCL") (pinfunction "SCL_SCL") (pintype "bidirectional"))
    )
    (net (code "101") (name "unconnected-(U$1-PadSCL1)") (class "Default")
      (node (ref "U$1") (pin "SCL1") (pinfunction "SCL1_SCL1") (pintype "bidirectional"))
    )
    (net (code "102") (name "unconnected-(U$1-PadSDA)") (class "Default")
      (node (ref "U$1") (pin "SDA") (pinfunction "SDA_SDA") (pintype "bidirectional"))
    )
    (net (code "103") (name "unconnected-(U$1-PadSDA1)") (class "Default")
      (node (ref "U$1") (pin "SDA1") (pinfunction "SDA1_SDA1") (pintype "bidirectional"))
    )
    (net (code "104") (name "unconnected-(U$1-PadTX0)") (class "Default")
      (node (ref "U$1") (pin "TX0") (pinfunction "TX0_TX0") (pintype "bidirectional"))
    )
    (net (code "105") (name "unconnected-(U$4A-R2OUT-Pad10)") (class "Default")
      (node (ref "U$4") (pin "10") (pinfunction "R2OUT_10") (pintype "output"))
    )
    (net (code "106") (name "unconnected-(U$4A-T2OUT-Pad8)") (class "Default")
      (node (ref "U$4") (pin "8") (pinfunction "T2OUT_8") (pintype "output"))
    )
    (net (code "107") (name "unconnected-(X2-Pad1)") (class "Default")
      (node (ref "X2") (pin "1") (pinfunction "1_1") (pintype "passive"))
    )
    (net (code "108") (name "unconnected-(X2-Pad6)") (class "Default")
      (node (ref "X2") (pin "6") (pinfunction "6_6") (pintype "passive"))
    )
    (net (code "109") (name "unconnected-(X2-Pad7)") (class "Default")
      (node (ref "X2") (pin "7") (pinfunction "7_7") (pintype "passive"))
    )
    (net (code "110") (name "~{RES_CEL1}") (class "Default")
      (node (ref "R9") (pin "2") (pinfunction "2_2") (pintype "passive"))
      (node (ref "U$1") (pin "4") (pinfunction "4_4") (pintype "bidirectional"))
    )
    (net (code "111") (name "~{RES_CEL2}") (class "Default")
      (node (ref "R10") (pin "2") (pinfunction "2_2") (pintype "passive"))
      (node (ref "U$1") (pin "3") (pinfunction "3_3") (pintype "bidirectional"))
    )
    (net (code "112") (name "~{RES_CEL3}") (class "Default")
      (node (ref "R11") (pin "2") (pinfunction "2_2") (pintype "passive"))
      (node (ref "U$1") (pin "5") (pinfunction "5_5") (pintype "bidirectional"))
    )
    (net (code "113") (name "~{RES_CEL4}") (class "Default")
      (node (ref "R14") (pin "2") (pinfunction "2_2") (pintype "passive"))
      (node (ref "U$1") (pin "6") (pinfunction "6_6") (pintype "bidirectional"))
    )
  )
)
